# PCB-Schematic.net
KiCad netlist of a schematic drawn in EAGLE
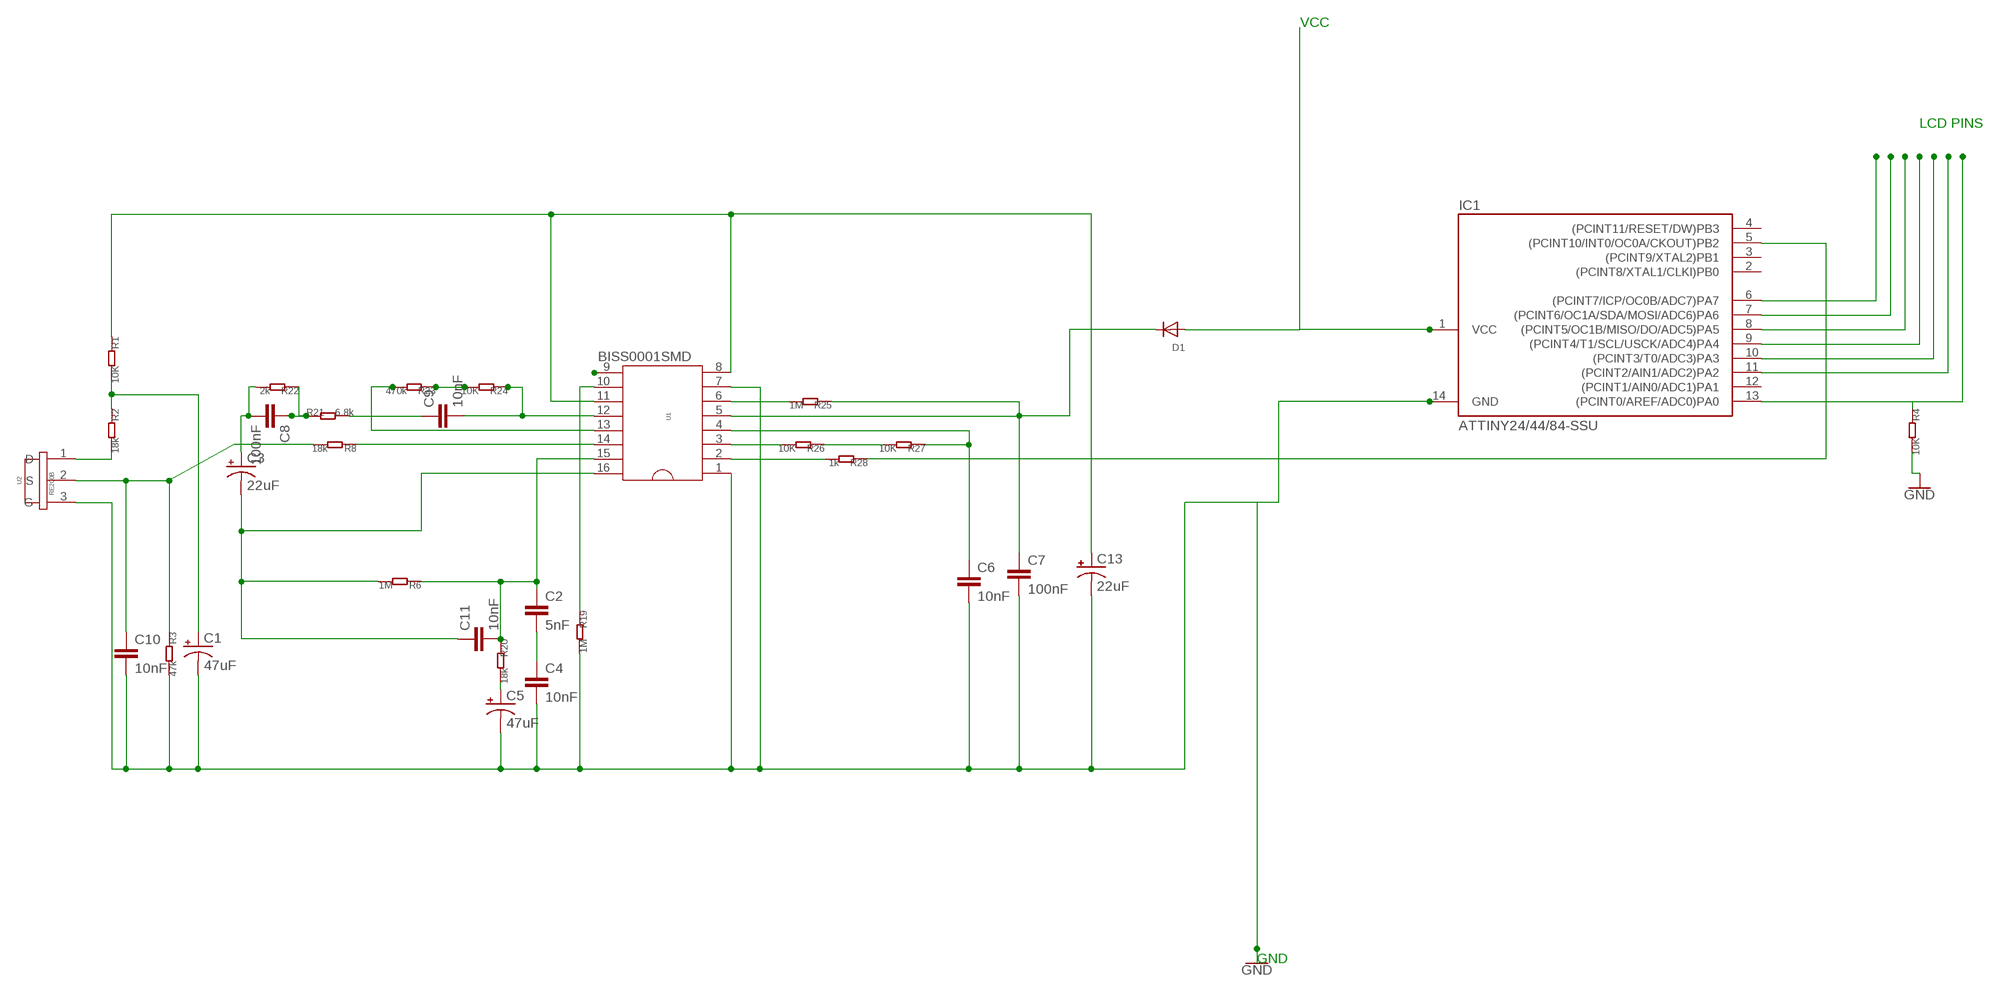
[diagram p0: schematic, sheet 1]

(export (version "E")
  (design (tool "Eeschema 10.0.6"))
  (components
    (comp (ref "C1")
      (value "47uF")
      (footprint "eagle-import:085CS_1W")
      (libsource (lib "eagle-import") (part "CPOL-US085CS-1W"))
    )
    (comp (ref "C2")
      (value "5nF")
      (footprint "eagle-import:C0805")
      (libsource (lib "eagle-import") (part "C"))
    )
    (comp (ref "C3")
      (value "22uF")
      (footprint "eagle-import:085CS_1W")
      (libsource (lib "eagle-import") (part "CPOL-US085CS-1W"))
    )
    (comp (ref "C4")
      (value "10nF")
      (footprint "eagle-import:C0805")
      (libsource (lib "eagle-import") (part "C"))
    )
    (comp (ref "C5")
      (value "47uF")
      (footprint "eagle-import:085CS_1W")
      (libsource (lib "eagle-import") (part "CPOL-US085CS-1W"))
    )
    (comp (ref "C6")
      (value "10nF")
      (footprint "eagle-import:C0805")
      (libsource (lib "eagle-import") (part "C"))
    )
    (comp (ref "C7")
      (value "100nF")
      (footprint "eagle-import:C0805")
      (libsource (lib "eagle-import") (part "C"))
    )
    (comp (ref "C8")
      (value "100nF")
      (footprint "eagle-import:C0805")
      (libsource (lib "eagle-import") (part "C"))
    )
    (comp (ref "C9")
      (value "10nF")
      (footprint "eagle-import:C0805")
      (libsource (lib "eagle-import") (part "C"))
    )
    (comp (ref "C10")
      (value "10nF")
      (footprint "eagle-import:C0805")
      (libsource (lib "eagle-import") (part "C"))
    )
    (comp (ref "C11")
      (value "10nF")
      (footprint "eagle-import:C0805")
      (libsource (lib "eagle-import") (part "C"))
    )
    (comp (ref "C13")
      (value "22uF")
      (footprint "eagle-import:085CS_1W")
      (libsource (lib "eagle-import") (part "CPOL-US085CS-1W"))
    )
    (comp (ref "D1")
      (value "DIODESOD-323F")
      (footprint "eagle-import:SOD-323F")
      (libsource (lib "eagle-import") (part "DIODESOD-323F"))
    )
    (comp (ref "IC1")
      (value "ATTINY24/44/84-SSU")
      (footprint "eagle-import:SOIC14")
      (libsource (lib "eagle-import") (part "ATTINY24/44/84-SSU"))
    )
    (comp (ref "R1")
      (value "10K")
      (footprint "eagle-import:R0603")
      (libsource (lib "eagle-import") (part "R-0603"))
    )
    (comp (ref "R2")
      (value "18k")
      (footprint "eagle-import:R0603")
      (libsource (lib "eagle-import") (part "R-0603"))
    )
    (comp (ref "R3")
      (value "47k")
      (footprint "eagle-import:R0603")
      (libsource (lib "eagle-import") (part "R-0603"))
    )
    (comp (ref "R4")
      (value "10K")
      (footprint "eagle-import:R0603")
      (libsource (lib "eagle-import") (part "R-0603"))
    )
    (comp (ref "R6")
      (value "1M")
      (footprint "eagle-import:R0603")
      (libsource (lib "eagle-import") (part "R-0603"))
    )
    (comp (ref "R8")
      (value "18k")
      (footprint "eagle-import:R0603")
      (libsource (lib "eagle-import") (part "R-0603"))
    )
    (comp (ref "R19")
      (value "1M")
      (footprint "eagle-import:R0603")
      (libsource (lib "eagle-import") (part "R-0603"))
    )
    (comp (ref "R20")
      (value "18k")
      (footprint "eagle-import:R0603")
      (libsource (lib "eagle-import") (part "R-0603"))
    )
    (comp (ref "R21")
      (value "6.8k")
      (footprint "eagle-import:R0603")
      (libsource (lib "eagle-import") (part "R-0603"))
    )
    (comp (ref "R22")
      (value "2k")
      (footprint "eagle-import:R0603")
      (libsource (lib "eagle-import") (part "R-0603"))
    )
    (comp (ref "R23")
      (value "470k")
      (footprint "eagle-import:R0603")
      (libsource (lib "eagle-import") (part "R-0603"))
    )
    (comp (ref "R24")
      (value "10K")
      (footprint "eagle-import:R0603")
      (libsource (lib "eagle-import") (part "R-0603"))
    )
    (comp (ref "R25")
      (value "1M")
      (footprint "eagle-import:R0603")
      (libsource (lib "eagle-import") (part "R-0603"))
    )
    (comp (ref "R26")
      (value "10K")
      (footprint "eagle-import:R0603")
      (libsource (lib "eagle-import") (part "R-0603"))
    )
    (comp (ref "R27")
      (value "10K")
      (footprint "eagle-import:R0603")
      (libsource (lib "eagle-import") (part "R-0603"))
    )
    (comp (ref "R28")
      (value "1k")
      (footprint "eagle-import:R0603")
      (libsource (lib "eagle-import") (part "R-0603"))
    )
    (comp (ref "U1")
      (value "BISS0001SMD")
      (footprint "eagle-import:SOP16")
      (libsource (lib "eagle-import") (part "BISS0001SMD"))
    )
    (comp (ref "U2")
      (value "RE200B")
      (footprint "eagle-import:RE200B")
      (libsource (lib "eagle-import") (part "RE200B"))
    )
  )
  (nets
    (net (code "1") (name "GND") (class "Default")
      (node (ref "C1") (pin "-") (pinfunction "-_-") (pintype "passive"))
      (node (ref "C10") (pin "2") (pinfunction "2_2") (pintype "passive"))
      (node (ref "C13") (pin "-") (pinfunction "-_-") (pintype "passive"))
      (node (ref "C4") (pin "2") (pinfunction "2_2") (pintype "passive"))
      (node (ref "C5") (pin "-") (pinfunction "-_-") (pintype "passive"))
      (node (ref "C6") (pin "2") (pinfunction "2_2") (pintype "passive"))
      (node (ref "C7") (pin "2") (pinfunction "2_2") (pintype "passive"))
      (node (ref "IC1") (pin "14") (pinfunction "GND_14") (pintype "power_in"))
      (node (ref "R19") (pin "2") (pinfunction "2_2") (pintype "passive"))
      (node (ref "R3") (pin "2") (pinfunction "2_2") (pintype "passive"))
      (node (ref "R4") (pin "2") (pinfunction "2_2") (pintype "passive"))
      (node (ref "U1") (pin "1") (pinfunction "P$1_1") (pintype "bidirectional"))
      (node (ref "U1") (pin "7") (pinfunction "P$7_7") (pintype "bidirectional"))
      (node (ref "U2") (pin "3") (pinfunction "G_3") (pintype "bidirectional"))
    )
    (net (code "2") (name "Net-(C1-Pad+)") (class "Default")
      (node (ref "C1") (pin "+") (pinfunction "+_+") (pintype "passive"))
      (node (ref "R1") (pin "2") (pinfunction "2_2") (pintype "passive"))
      (node (ref "R2") (pin "1") (pinfunction "1_1") (pintype "passive"))
    )
    (net (code "3") (name "Net-(C2-Pad2)") (class "Default")
      (node (ref "C2") (pin "2") (pinfunction "2_2") (pintype "passive"))
      (node (ref "C4") (pin "1") (pinfunction "1_1") (pintype "passive"))
    )
    (net (code "4") (name "Net-(C3-Pad+)") (class "Default")
      (node (ref "C3") (pin "+") (pinfunction "+_+") (pintype "passive"))
      (node (ref "C8") (pin "2") (pinfunction "2_2") (pintype "passive"))
      (node (ref "R22") (pin "2") (pinfunction "2_2") (pintype "passive"))
    )
    (net (code "5") (name "Net-(C5-Pad+)") (class "Default")
      (node (ref "C5") (pin "+") (pinfunction "+_+") (pintype "passive"))
      (node (ref "R20") (pin "2") (pinfunction "2_2") (pintype "passive"))
    )
    (net (code "6") (name "Net-(C8-Pad1)") (class "Default")
      (node (ref "C8") (pin "1") (pinfunction "1_1") (pintype "passive"))
      (node (ref "R21") (pin "1") (pinfunction "1_1") (pintype "passive"))
      (node (ref "R22") (pin "1") (pinfunction "1_1") (pintype "passive"))
    )
    (net (code "7") (name "Net-(C9-Pad1)") (class "Default")
      (node (ref "C9") (pin "1") (pinfunction "1_1") (pintype "passive"))
      (node (ref "R21") (pin "2") (pinfunction "2_2") (pintype "passive"))
    )
    (net (code "8") (name "Net-(IC1-(PCINT0{slash}AREF{slash}ADC0)PA0)") (class "Default")
      (node (ref "IC1") (pin "13") (pinfunction "(PCINT0/AREF/ADC0)PA0_13") (pintype "bidirectional"))
      (node (ref "R4") (pin "1") (pinfunction "1_1") (pintype "passive"))
    )
    (net (code "9") (name "Net-(IC1-(PCINT10{slash}INT0{slash}OC0A{slash}CKOUT)PB2)") (class "Default")
      (node (ref "IC1") (pin "5") (pinfunction "(PCINT10/INT0/OC0A/CKOUT)PB2_5") (pintype "bidirectional"))
      (node (ref "R28") (pin "1") (pinfunction "1_1") (pintype "passive"))
    )
    (net (code "10") (name "Net-(IC1-VCC)") (class "Default")
      (node (ref "D1") (pin "A") (pinfunction "A_A") (pintype "passive"))
      (node (ref "IC1") (pin "1") (pinfunction "VCC_1") (pintype "power_in"))
    )
    (net (code "11") (name "Net-(R23-Pad1)") (class "Default")
      (node (ref "R23") (pin "1") (pinfunction "1_1") (pintype "passive"))
      (node (ref "R24") (pin "2") (pinfunction "2_2") (pintype "passive"))
    )
    (net (code "12") (name "Net-(R26-Pad1)") (class "Default")
      (node (ref "R26") (pin "1") (pinfunction "1_1") (pintype "passive"))
      (node (ref "R27") (pin "2") (pinfunction "2_2") (pintype "passive"))
    )
    (net (code "13") (name "Net-(U1-P$2)") (class "Default")
      (node (ref "R28") (pin "2") (pinfunction "2_2") (pintype "passive"))
      (node (ref "U1") (pin "2") (pinfunction "P$2_2") (pintype "bidirectional"))
    )
    (net (code "14") (name "Net-(U1-P$3)") (class "Default")
      (node (ref "R26") (pin "2") (pinfunction "2_2") (pintype "passive"))
      (node (ref "U1") (pin "3") (pinfunction "P$3_3") (pintype "bidirectional"))
    )
    (net (code "15") (name "Net-(U1-P$4)") (class "Default")
      (node (ref "C6") (pin "1") (pinfunction "1_1") (pintype "passive"))
      (node (ref "R27") (pin "1") (pinfunction "1_1") (pintype "passive"))
      (node (ref "U1") (pin "4") (pinfunction "P$4_4") (pintype "bidirectional"))
    )
    (net (code "16") (name "Net-(U1-P$5)") (class "Default")
      (node (ref "C7") (pin "1") (pinfunction "1_1") (pintype "passive"))
      (node (ref "D1") (pin "C") (pinfunction "C_C") (pintype "passive"))
      (node (ref "R25") (pin "1") (pinfunction "1_1") (pintype "passive"))
      (node (ref "U1") (pin "5") (pinfunction "P$5_5") (pintype "bidirectional"))
    )
    (net (code "17") (name "Net-(U1-P$6)") (class "Default")
      (node (ref "R25") (pin "2") (pinfunction "2_2") (pintype "passive"))
      (node (ref "U1") (pin "6") (pinfunction "P$6_6") (pintype "bidirectional"))
    )
    (net (code "18") (name "Net-(U1-P$10)") (class "Default")
      (node (ref "R19") (pin "1") (pinfunction "1_1") (pintype "passive"))
      (node (ref "U1") (pin "10") (pinfunction "P$10_10") (pintype "bidirectional"))
    )
    (net (code "19") (name "Net-(U1-P$11)") (class "Default")
      (node (ref "C13") (pin "+") (pinfunction "+_+") (pintype "passive"))
      (node (ref "R1") (pin "1") (pinfunction "1_1") (pintype "passive"))
      (node (ref "U1") (pin "11") (pinfunction "P$11_11") (pintype "bidirectional"))
      (node (ref "U1") (pin "8") (pinfunction "P$8_8") (pintype "bidirectional"))
    )
    (net (code "20") (name "Net-(U1-P$12)") (class "Default")
      (node (ref "C9") (pin "2") (pinfunction "2_2") (pintype "passive"))
      (node (ref "R24") (pin "1") (pinfunction "1_1") (pintype "passive"))
      (node (ref "U1") (pin "12") (pinfunction "P$12_12") (pintype "bidirectional"))
    )
    (net (code "21") (name "Net-(U1-P$13)") (class "Default")
      (node (ref "R23") (pin "2") (pinfunction "2_2") (pintype "passive"))
      (node (ref "U1") (pin "13") (pinfunction "P$13_13") (pintype "bidirectional"))
    )
    (net (code "22") (name "Net-(U1-P$14)") (class "Default")
      (node (ref "R8") (pin "1") (pinfunction "1_1") (pintype "passive"))
      (node (ref "U1") (pin "14") (pinfunction "P$14_14") (pintype "bidirectional"))
    )
    (net (code "23") (name "Net-(U1-P$15)") (class "Default")
      (node (ref "C11") (pin "2") (pinfunction "2_2") (pintype "passive"))
      (node (ref "C2") (pin "1") (pinfunction "1_1") (pintype "passive"))
      (node (ref "R20") (pin "1") (pinfunction "1_1") (pintype "passive"))
      (node (ref "R6") (pin "1") (pinfunction "1_1") (pintype "passive"))
      (node (ref "U1") (pin "15") (pinfunction "P$15_15") (pintype "bidirectional"))
    )
    (net (code "24") (name "Net-(U1-P$16)") (class "Default")
      (node (ref "C11") (pin "1") (pinfunction "1_1") (pintype "passive"))
      (node (ref "C3") (pin "-") (pinfunction "-_-") (pintype "passive"))
      (node (ref "R6") (pin "2") (pinfunction "2_2") (pintype "passive"))
      (node (ref "U1") (pin "16") (pinfunction "P$16_16") (pintype "bidirectional"))
    )
    (net (code "25") (name "Net-(U2-D)") (class "Default")
      (node (ref "R2") (pin "2") (pinfunction "2_2") (pintype "passive"))
      (node (ref "U2") (pin "1") (pinfunction "D_1") (pintype "bidirectional"))
    )
    (net (code "26") (name "Net-(U2-S)") (class "Default")
      (node (ref "C10") (pin "1") (pinfunction "1_1") (pintype "passive"))
      (node (ref "R3") (pin "1") (pinfunction "1_1") (pintype "passive"))
      (node (ref "R8") (pin "2") (pinfunction "2_2") (pintype "passive"))
      (node (ref "U2") (pin "2") (pinfunction "S_2") (pintype "bidirectional"))
    )
    (net (code "27") (name "unconnected-(IC1-(PCINT1{slash}AIN0{slash}ADC1)PA1-Pad12)") (class "Default")
      (node (ref "IC1") (pin "12") (pinfunction "(PCINT1/AIN0/ADC1)PA1_12") (pintype "bidirectional"))
    )
    (net (code "28") (name "unconnected-(IC1-(PCINT2{slash}AIN1{slash}ADC2)PA2-Pad11)") (class "Default")
      (node (ref "IC1") (pin "11") (pinfunction "(PCINT2/AIN1/ADC2)PA2_11") (pintype "bidirectional"))
    )
    (net (code "29") (name "unconnected-(IC1-(PCINT3{slash}T0{slash}ADC3)PA3-Pad10)") (class "Default")
      (node (ref "IC1") (pin "10") (pinfunction "(PCINT3/T0/ADC3)PA3_10") (pintype "bidirectional"))
    )
    (net (code "30") (name "unconnected-(IC1-(PCINT4{slash}T1{slash}SCL{slash}USCK{slash}ADC4)PA4-Pad9)") (class "Default")
      (node (ref "IC1") (pin "9") (pinfunction "(PCINT4/T1/SCL/USCK/ADC4)PA4_9") (pintype "bidirectional"))
    )
    (net (code "31") (name "unconnected-(IC1-(PCINT5{slash}OC1B{slash}MISO{slash}DO{slash}ADC5)PA5-Pad8)") (class "Default")
      (node (ref "IC1") (pin "8") (pinfunction "(PCINT5/OC1B/MISO/DO/ADC5)PA5_8") (pintype "bidirectional"))
    )
    (net (code "32") (name "unconnected-(IC1-(PCINT6{slash}OC1A{slash}SDA{slash}MOSI{slash}ADC6)PA6-Pad7)") (class "Default")
      (node (ref "IC1") (pin "7") (pinfunction "(PCINT6/OC1A/SDA/MOSI/ADC6)PA6_7") (pintype "bidirectional"))
    )
    (net (code "33") (name "unconnected-(IC1-(PCINT7{slash}ICP{slash}OC0B{slash}ADC7)PA7-Pad6)") (class "Default")
      (node (ref "IC1") (pin "6") (pinfunction "(PCINT7/ICP/OC0B/ADC7)PA7_6") (pintype "bidirectional"))
    )
    (net (code "34") (name "unconnected-(IC1-(PCINT8{slash}XTAL1{slash}CLKI)PB0-Pad2)") (class "Default")
      (node (ref "IC1") (pin "2") (pinfunction "(PCINT8/XTAL1/CLKI)PB0_2") (pintype "bidirectional"))
    )
    (net (code "35") (name "unconnected-(IC1-(PCINT9{slash}XTAL2)PB1-Pad3)") (class "Default")
      (node (ref "IC1") (pin "3") (pinfunction "(PCINT9/XTAL2)PB1_3") (pintype "bidirectional"))
    )
    (net (code "36") (name "unconnected-(IC1-(PCINT11{slash}RESET{slash}DW)PB3-Pad4)") (class "Default")
      (node (ref "IC1") (pin "4") (pinfunction "(PCINT11/RESET/DW)PB3_4") (pintype "bidirectional"))
    )
    (net (code "37") (name "unconnected-(U1-P$9-Pad9)") (class "Default")
      (node (ref "U1") (pin "9") (pinfunction "P$9_9") (pintype "bidirectional"))
    )
  )
)
